# CLKB_main.net
KiCad netlist of a schematic drawn in Altium Designer
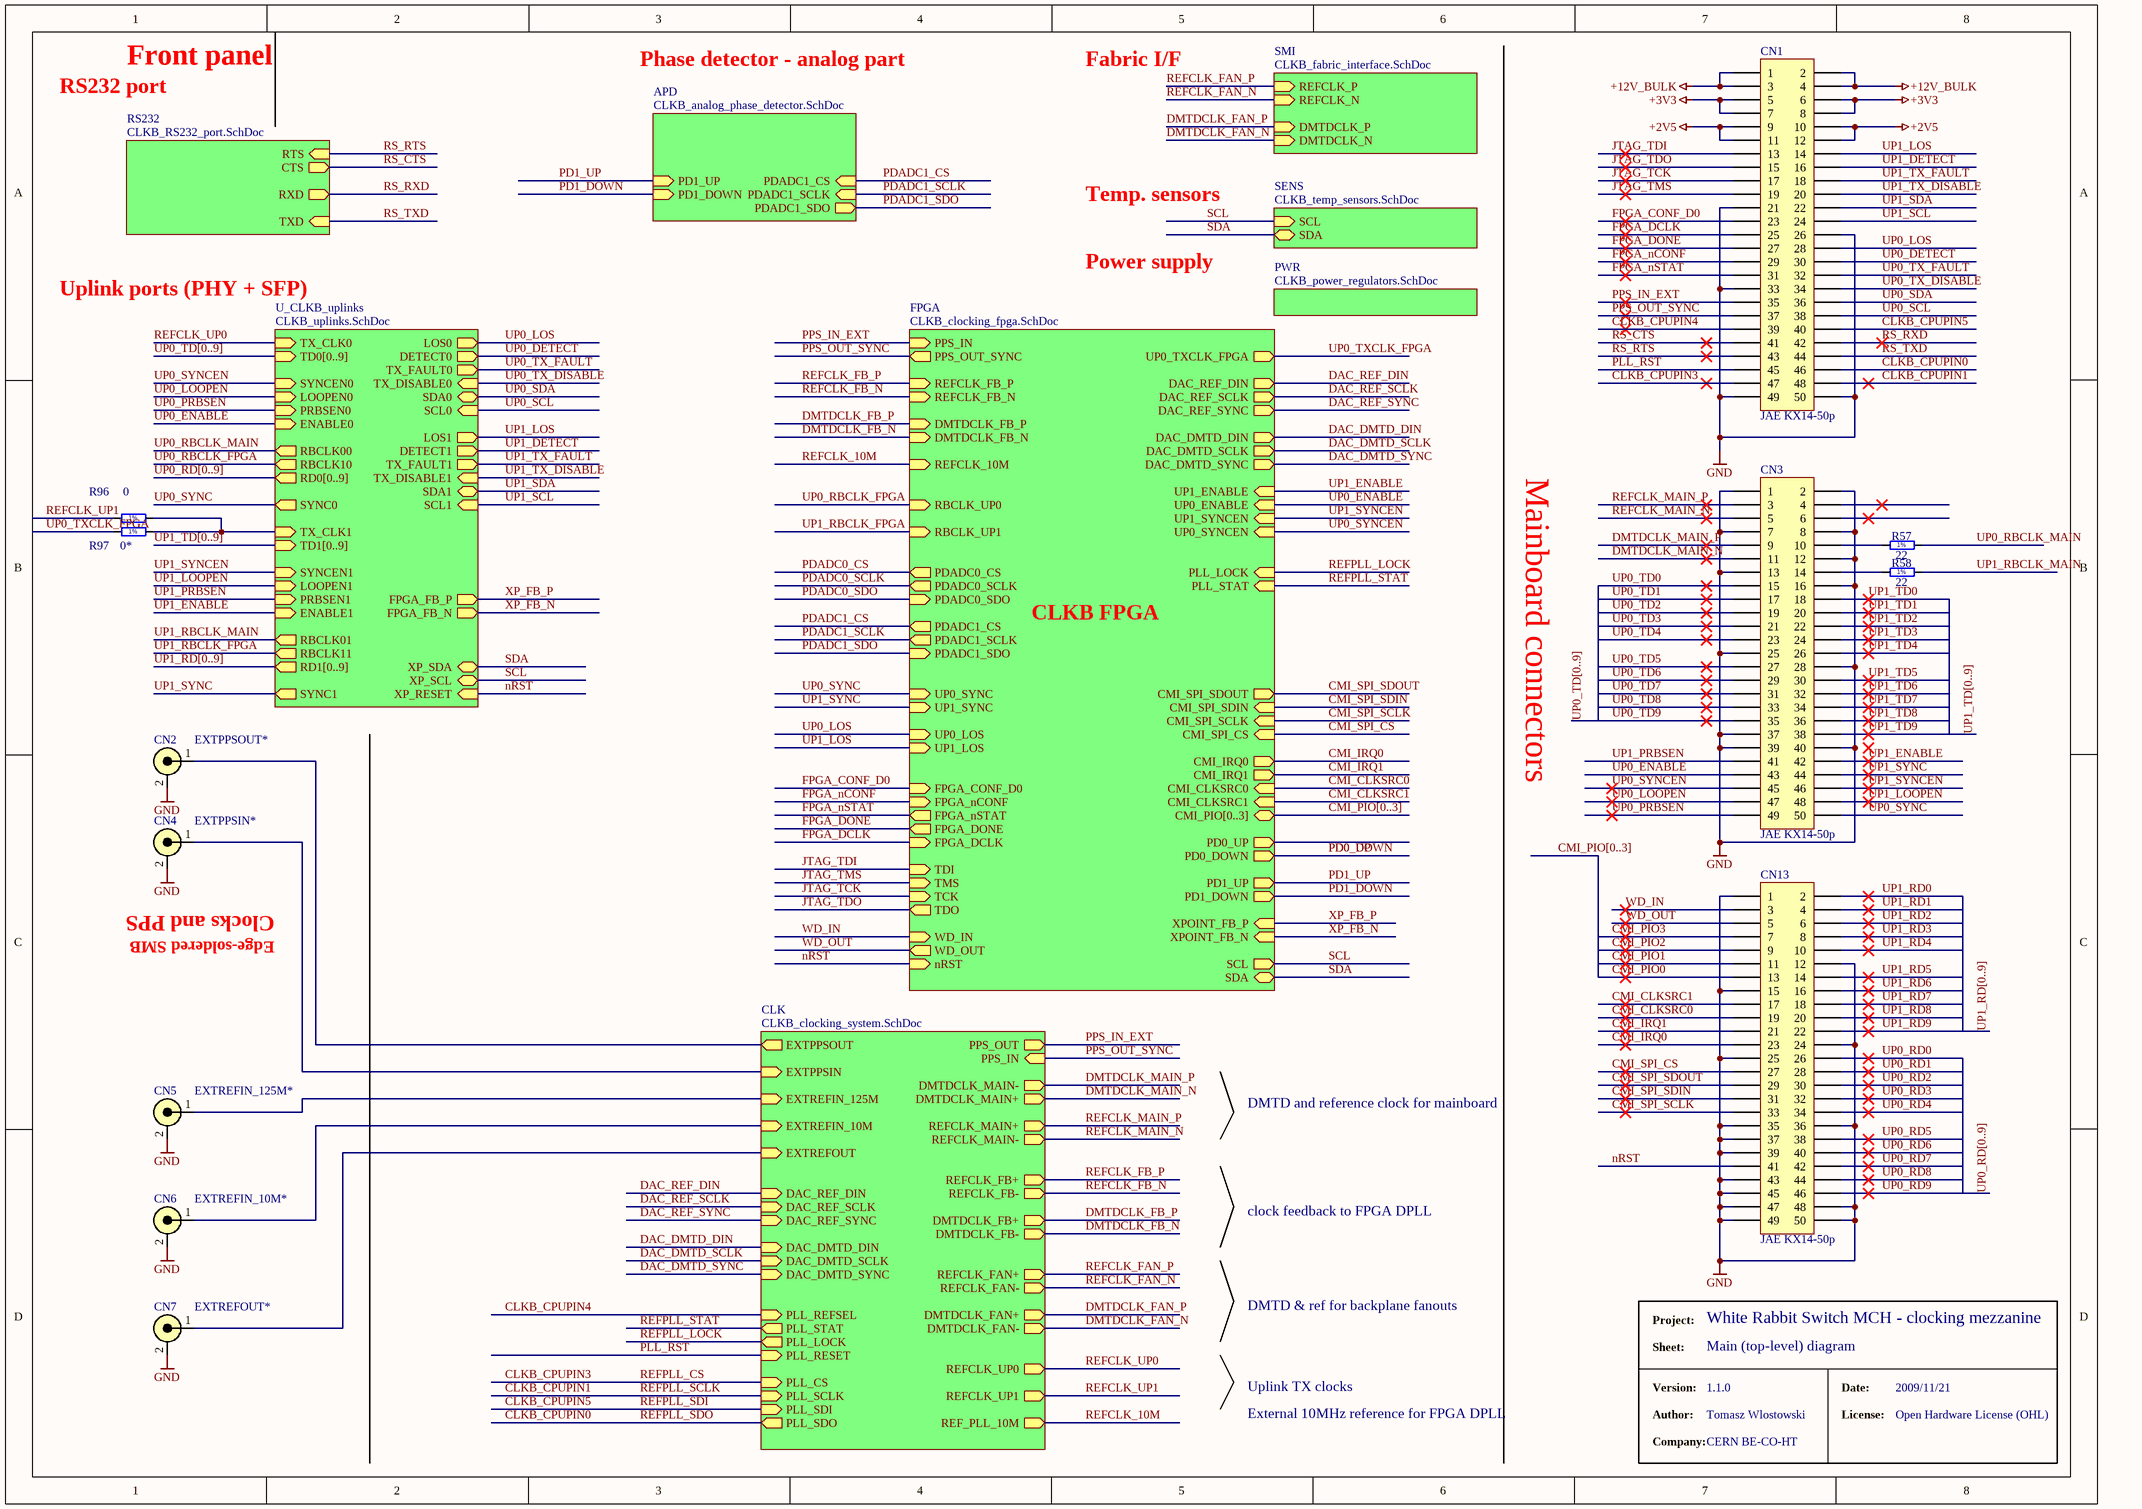
[diagram p0: CLKB_main.SchDoc]

(export (version "E")
  (design (tool "Eeschema 10.0.6"))
  (components
    (comp (ref "CN1")
      (value "JAE KX14-50p")
      (footprint "JAE_KX14_50P")
      (description "multipin B2B connector (plug)")
      (libsource (lib "wr_switch") (part "KX14_50p"))
    )
    (comp (ref "CN2")
      (value "EXTPPSOUT*")
      (footprint "MCH_SPECIAL_FP_CLOCKS")
      (description "SMB piggyboard connection")
      (libsource (lib "wr_switch") (part "SMA_SOCKET"))
    )
    (comp (ref "CN3")
      (value "JAE KX14-50p")
      (footprint "JAE_KX14_50P")
      (description "multipin B2B connector (plug)")
      (libsource (lib "wr_switch") (part "KX14_50p"))
    )
    (comp (ref "CN4")
      (value "EXTPPSIN*")
      (footprint "MCH_SPECIAL_FP_CLOCKS")
      (description "SMB piggyboard connection")
      (libsource (lib "wr_switch") (part "SMA_SOCKET"))
    )
    (comp (ref "CN5")
      (value "EXTREFIN_125M*")
      (footprint "MCH_SPECIAL_FP_CLOCKS")
      (description "SMB piggyboard connection")
      (libsource (lib "wr_switch") (part "SMA_SOCKET"))
    )
    (comp (ref "CN6")
      (value "EXTREFIN_10M*")
      (footprint "MCH_SPECIAL_FP_CLOCKS")
      (description "SMB piggyboard connection")
      (libsource (lib "wr_switch") (part "SMA_SOCKET"))
    )
    (comp (ref "CN7")
      (value "EXTREFOUT*")
      (footprint "MCH_SPECIAL_FP_CLOCKS")
      (description "SMB piggyboard connection")
      (libsource (lib "wr_switch") (part "SMA_SOCKET"))
    )
    (comp (ref "CN13")
      (value "JAE KX14-50p")
      (footprint "JAE_KX14_50P")
      (description "multipin B2B connector (plug)")
      (libsource (lib "wr_switch") (part "KX14_50p"))
    )
    (comp (ref "R57")
      (value "22")
      (footprint "RESC1608X55N")
      (description "Resistor - 1%")
      (fields
        (field (name "PART NUMBER") "R0603_22R_1%_0.1W_100PPM")
        (field (name "POWER") "0.1W")
        (field (name "AUTHOR") "CERN DEM JLC")
      )
      (libsource (lib "Resistors") (part "Resistor - 1%"))
    )
    (comp (ref "R58")
      (value "22")
      (footprint "RESC1608X55N")
      (description "Resistor - 1%")
      (fields
        (field (name "PART NUMBER") "R0603_22R_1%_0.1W_100PPM")
        (field (name "POWER") "0.1W")
        (field (name "AUTHOR") "CERN DEM JLC")
      )
      (libsource (lib "Resistors") (part "Resistor - 1%"))
    )
    (comp (ref "R96")
      (value "0")
      (footprint "RESC1005X40N")
      (description "Resistor - 1%")
      (fields
        (field (name "PART NUMBER") "R0402_0R_JUMPER")
        (field (name "MANUFACTURER") "GENERIC")
        (field (name "AUTHOR") "CERN DEM JLC")
      )
      (libsource (lib "Resistors") (part "Resistor - 1%"))
    )
    (comp (ref "R97")
      (value "0*")
      (footprint "RESC1005X40N")
      (description "Resistor - 1%")
      (fields
        (field (name "PART NUMBER") "R0402_0R_JUMPER")
        (field (name "MANUFACTURER") "GENERIC")
        (field (name "AUTHOR") "CERN DEM JLC")
      )
      (libsource (lib "Resistors") (part "Resistor - 1%"))
    )
  )
  (nets
    (net (code "1") (name "+2V5") (class "Default")
      (node (ref "CN1") (pin "10") (pinfunction "10_10") (pintype "passive"))
      (node (ref "CN1") (pin "11") (pinfunction "11_11") (pintype "passive"))
      (node (ref "CN1") (pin "12") (pinfunction "12_12") (pintype "passive"))
      (node (ref "CN1") (pin "9") (pinfunction "9_9") (pintype "passive"))
    )
    (net (code "2") (name "+3V3") (class "Default")
      (node (ref "CN1") (pin "5") (pinfunction "5_5") (pintype "passive"))
      (node (ref "CN1") (pin "6") (pinfunction "6_6") (pintype "passive"))
      (node (ref "CN1") (pin "7") (pinfunction "7_7") (pintype "passive"))
      (node (ref "CN1") (pin "8") (pinfunction "8_8") (pintype "passive"))
    )
    (net (code "3") (name "+12V_BULK") (class "Default")
      (node (ref "CN1") (pin "1") (pinfunction "1_1") (pintype "passive"))
      (node (ref "CN1") (pin "2") (pinfunction "2_2") (pintype "passive"))
      (node (ref "CN1") (pin "3") (pinfunction "3_3") (pintype "passive"))
      (node (ref "CN1") (pin "4") (pinfunction "4_4") (pintype "passive"))
    )
    (net (code "4") (name "/CLKB_CPUPIN0") (class "Default")
      (node (ref "CN1") (pin "46") (pinfunction "46_46") (pintype "passive"))
    )
    (net (code "5") (name "/CLKB_CPUPIN1") (class "Default")
      (node (ref "CN1") (pin "48") (pinfunction "48_48") (pintype "passive"))
    )
    (net (code "6") (name "/CLKB_CPUPIN3") (class "Default")
      (node (ref "CN1") (pin "47") (pinfunction "47_47") (pintype "passive"))
    )
    (net (code "7") (name "/CLKB_CPUPIN4") (class "Default")
      (node (ref "CN1") (pin "39") (pinfunction "39_39") (pintype "passive"))
    )
    (net (code "8") (name "/CLKB_CPUPIN5") (class "Default")
      (node (ref "CN1") (pin "40") (pinfunction "40_40") (pintype "passive"))
    )
    (net (code "9") (name "/CMI_CLKSRC0") (class "Default")
      (node (ref "CN13") (pin "19") (pinfunction "19_19") (pintype "passive"))
    )
    (net (code "10") (name "/CMI_CLKSRC1") (class "Default")
      (node (ref "CN13") (pin "17") (pinfunction "17_17") (pintype "passive"))
    )
    (net (code "11") (name "/CMI_IRQ0") (class "Default")
      (node (ref "CN13") (pin "23") (pinfunction "23_23") (pintype "passive"))
    )
    (net (code "12") (name "/CMI_IRQ1") (class "Default")
      (node (ref "CN13") (pin "21") (pinfunction "21_21") (pintype "passive"))
    )
    (net (code "13") (name "/CMI_PIO0") (class "Default")
      (node (ref "CN13") (pin "13") (pinfunction "13_13") (pintype "passive"))
    )
    (net (code "14") (name "/CMI_PIO1") (class "Default")
      (node (ref "CN13") (pin "11") (pinfunction "11_11") (pintype "passive"))
    )
    (net (code "15") (name "/CMI_PIO2") (class "Default")
      (node (ref "CN13") (pin "9") (pinfunction "9_9") (pintype "passive"))
    )
    (net (code "16") (name "/CMI_PIO3") (class "Default")
      (node (ref "CN13") (pin "7") (pinfunction "7_7") (pintype "passive"))
    )
    (net (code "18") (name "/CMI_SPI_CS") (class "Default")
      (node (ref "CN13") (pin "27") (pinfunction "27_27") (pintype "passive"))
    )
    (net (code "19") (name "/CMI_SPI_SCLK") (class "Default")
      (node (ref "CN13") (pin "33") (pinfunction "33_33") (pintype "passive"))
    )
    (net (code "20") (name "/CMI_SPI_SDIN") (class "Default")
      (node (ref "CN13") (pin "31") (pinfunction "31_31") (pintype "passive"))
    )
    (net (code "21") (name "/CMI_SPI_SDOUT") (class "Default")
      (node (ref "CN13") (pin "29") (pinfunction "29_29") (pintype "passive"))
    )
    (net (code "32") (name "/DMTDCLK_MAIN_N") (class "Default")
      (node (ref "CN3") (pin "11") (pinfunction "11_11") (pintype "passive"))
    )
    (net (code "33") (name "/DMTDCLK_MAIN_P") (class "Default")
      (node (ref "CN3") (pin "9") (pinfunction "9_9") (pintype "passive"))
    )
    (net (code "34") (name "/EXTPPSIN") (class "Default")
      (node (ref "CN4") (pin "1") (pinfunction "HOT_1") (pintype "passive"))
    )
    (net (code "35") (name "/EXTPPSOUT") (class "Default")
      (node (ref "CN2") (pin "1") (pinfunction "HOT_1") (pintype "passive"))
    )
    (net (code "36") (name "/EXTREFIN_10M") (class "Default")
      (node (ref "CN6") (pin "1") (pinfunction "HOT_1") (pintype "passive"))
    )
    (net (code "37") (name "/EXTREFIN_125M") (class "Default")
      (node (ref "CN5") (pin "1") (pinfunction "HOT_1") (pintype "passive"))
    )
    (net (code "38") (name "/EXTREFOUT") (class "Default")
      (node (ref "CN7") (pin "1") (pinfunction "HOT_1") (pintype "passive"))
    )
    (net (code "39") (name "/FPGA_CONF_D0") (class "Default")
      (node (ref "CN1") (pin "23") (pinfunction "23_23") (pintype "passive"))
    )
    (net (code "40") (name "/FPGA_DCLK") (class "Default")
      (node (ref "CN1") (pin "25") (pinfunction "25_25") (pintype "passive"))
    )
    (net (code "41") (name "/FPGA_DONE") (class "Default")
      (node (ref "CN1") (pin "27") (pinfunction "27_27") (pintype "passive"))
    )
    (net (code "42") (name "/FPGA_nCONF") (class "Default")
      (node (ref "CN1") (pin "29") (pinfunction "29_29") (pintype "passive"))
    )
    (net (code "43") (name "/FPGA_nSTAT") (class "Default")
      (node (ref "CN1") (pin "31") (pinfunction "31_31") (pintype "passive"))
    )
    (net (code "44") (name "/JTAG_TCK") (class "Default")
      (node (ref "CN1") (pin "17") (pinfunction "17_17") (pintype "passive"))
    )
    (net (code "45") (name "/JTAG_TDI") (class "Default")
      (node (ref "CN1") (pin "13") (pinfunction "13_13") (pintype "passive"))
    )
    (net (code "46") (name "/JTAG_TDO") (class "Default")
      (node (ref "CN1") (pin "15") (pinfunction "15_15") (pintype "passive"))
    )
    (net (code "47") (name "/JTAG_TMS") (class "Default")
      (node (ref "CN1") (pin "19") (pinfunction "19_19") (pintype "passive"))
    )
    (net (code "57") (name "/PLL_RST") (class "Default")
      (node (ref "CN1") (pin "45") (pinfunction "45_45") (pintype "passive"))
    )
    (net (code "58") (name "/PPS_IN_EXT") (class "Default")
      (node (ref "CN1") (pin "35") (pinfunction "35_35") (pintype "passive"))
    )
    (net (code "59") (name "/PPS_OUT_SYNC") (class "Default")
      (node (ref "CN1") (pin "37") (pinfunction "37_37") (pintype "passive"))
    )
    (net (code "65") (name "/REFCLK_MAIN_N") (class "Default")
      (node (ref "CN3") (pin "5") (pinfunction "5_5") (pintype "passive"))
    )
    (net (code "66") (name "/REFCLK_MAIN_P") (class "Default")
      (node (ref "CN3") (pin "3") (pinfunction "3_3") (pintype "passive"))
    )
    (net (code "68") (name "/REFCLK_UP1") (class "Default")
      (node (ref "R96") (pin "1") (pinfunction "1_1") (pintype "passive"))
    )
    (net (code "71") (name "/RS_CTS") (class "Default")
      (node (ref "CN1") (pin "41") (pinfunction "41_41") (pintype "passive"))
    )
    (net (code "72") (name "/RS_RTS") (class "Default")
      (node (ref "CN1") (pin "43") (pinfunction "43_43") (pintype "passive"))
    )
    (net (code "74") (name "/RS_RXD") (class "Default")
      (node (ref "CN1") (pin "42") (pinfunction "42_42") (pintype "passive"))
    )
    (net (code "77") (name "/RS_TXD") (class "Default")
      (node (ref "CN1") (pin "44") (pinfunction "44_44") (pintype "passive"))
    )
    (net (code "78") (name "/TX_CLK1") (class "Default")
      (node (ref "R96") (pin "2") (pinfunction "2_2") (pintype "passive"))
      (node (ref "R97") (pin "2") (pinfunction "2_2") (pintype "passive"))
    )
    (net (code "79") (name "/UP0_DETECT") (class "Default")
      (node (ref "CN1") (pin "30") (pinfunction "30_30") (pintype "passive"))
    )
    (net (code "81") (name "/UP0_ENABLE") (class "Default")
      (node (ref "CN3") (pin "43") (pinfunction "43_43") (pintype "passive"))
    )
    (net (code "84") (name "/UP0_LOOPEN") (class "Default")
      (node (ref "CN3") (pin "47") (pinfunction "47_47") (pintype "passive"))
    )
    (net (code "85") (name "/UP0_LOS") (class "Default")
      (node (ref "CN1") (pin "28") (pinfunction "28_28") (pintype "passive"))
    )
    (net (code "86") (name "/UP0_PRBSEN") (class "Default")
      (node (ref "CN3") (pin "49") (pinfunction "49_49") (pintype "passive"))
    )
    (net (code "87") (name "/UP0_RBCLK_MAIN") (class "Default")
      (node (ref "R57") (pin "2") (pinfunction "2_2") (pintype "passive"))
    )
    (net (code "88") (name "/UP0_RD0") (class "Default")
      (node (ref "CN13") (pin "26") (pinfunction "26_26") (pintype "passive"))
    )
    (net (code "89") (name "/UP0_RD1") (class "Default")
      (node (ref "CN13") (pin "28") (pinfunction "28_28") (pintype "passive"))
    )
    (net (code "90") (name "/UP0_RD2") (class "Default")
      (node (ref "CN13") (pin "30") (pinfunction "30_30") (pintype "passive"))
    )
    (net (code "91") (name "/UP0_RD3") (class "Default")
      (node (ref "CN13") (pin "32") (pinfunction "32_32") (pintype "passive"))
    )
    (net (code "92") (name "/UP0_RD4") (class "Default")
      (node (ref "CN13") (pin "34") (pinfunction "34_34") (pintype "passive"))
    )
    (net (code "93") (name "/UP0_RD5") (class "Default")
      (node (ref "CN13") (pin "38") (pinfunction "38_38") (pintype "passive"))
    )
    (net (code "94") (name "/UP0_RD6") (class "Default")
      (node (ref "CN13") (pin "40") (pinfunction "40_40") (pintype "passive"))
    )
    (net (code "96") (name "/UP0_RD7") (class "Default")
      (node (ref "CN13") (pin "42") (pinfunction "42_42") (pintype "passive"))
    )
    (net (code "97") (name "/UP0_RD8") (class "Default")
      (node (ref "CN13") (pin "44") (pinfunction "44_44") (pintype "passive"))
    )
    (net (code "98") (name "/UP0_RD9") (class "Default")
      (node (ref "CN13") (pin "46") (pinfunction "46_46") (pintype "passive"))
    )
    (net (code "100") (name "/UP0_SCL") (class "Default")
      (node (ref "CN1") (pin "38") (pinfunction "38_38") (pintype "passive"))
    )
    (net (code "101") (name "/UP0_SDA") (class "Default")
      (node (ref "CN1") (pin "36") (pinfunction "36_36") (pintype "passive"))
    )
    (net (code "102") (name "/UP0_SYNC") (class "Default")
      (node (ref "CN3") (pin "50") (pinfunction "50_50") (pintype "passive"))
    )
    (net (code "103") (name "/UP0_SYNCEN") (class "Default")
      (node (ref "CN3") (pin "45") (pinfunction "45_45") (pintype "passive"))
    )
    (net (code "104") (name "/UP0_TD0") (class "Default")
      (node (ref "CN3") (pin "15") (pinfunction "15_15") (pintype "passive"))
    )
    (net (code "105") (name "/UP0_TD1") (class "Default")
      (node (ref "CN3") (pin "17") (pinfunction "17_17") (pintype "passive"))
    )
    (net (code "106") (name "/UP0_TD2") (class "Default")
      (node (ref "CN3") (pin "19") (pinfunction "19_19") (pintype "passive"))
    )
    (net (code "107") (name "/UP0_TD3") (class "Default")
      (node (ref "CN3") (pin "21") (pinfunction "21_21") (pintype "passive"))
    )
    (net (code "108") (name "/UP0_TD4") (class "Default")
      (node (ref "CN3") (pin "23") (pinfunction "23_23") (pintype "passive"))
    )
    (net (code "109") (name "/UP0_TD5") (class "Default")
      (node (ref "CN3") (pin "27") (pinfunction "27_27") (pintype "passive"))
    )
    (net (code "111") (name "/UP0_TD6") (class "Default")
      (node (ref "CN3") (pin "29") (pinfunction "29_29") (pintype "passive"))
    )
    (net (code "112") (name "/UP0_TD7") (class "Default")
      (node (ref "CN3") (pin "31") (pinfunction "31_31") (pintype "passive"))
    )
    (net (code "113") (name "/UP0_TD8") (class "Default")
      (node (ref "CN3") (pin "33") (pinfunction "33_33") (pintype "passive"))
    )
    (net (code "114") (name "/UP0_TD9") (class "Default")
      (node (ref "CN3") (pin "35") (pinfunction "35_35") (pintype "passive"))
    )
    (net (code "117") (name "/UP0_TXCLK_FPGA") (class "Default")
      (node (ref "R97") (pin "1") (pinfunction "1_1") (pintype "passive"))
    )
    (net (code "118") (name "/UP0_TX_DISABLE") (class "Default")
      (node (ref "CN1") (pin "34") (pinfunction "34_34") (pintype "passive"))
    )
    (net (code "120") (name "/UP0_TX_FAULT") (class "Default")
      (node (ref "CN1") (pin "32") (pinfunction "32_32") (pintype "passive"))
    )
    (net (code "121") (name "/UP1_DETECT") (class "Default")
      (node (ref "CN1") (pin "16") (pinfunction "16_16") (pintype "passive"))
    )
    (net (code "122") (name "/UP1_ENABLE") (class "Default")
      (node (ref "CN3") (pin "42") (pinfunction "42_42") (pintype "passive"))
    )
    (net (code "123") (name "/UP1_LOOPEN") (class "Default")
      (node (ref "CN3") (pin "48") (pinfunction "48_48") (pintype "passive"))
    )
    (net (code "124") (name "/UP1_LOS") (class "Default")
      (node (ref "CN1") (pin "14") (pinfunction "14_14") (pintype "passive"))
    )
    (net (code "125") (name "/UP1_PRBSEN") (class "Default")
      (node (ref "CN3") (pin "41") (pinfunction "41_41") (pintype "passive"))
    )
    (net (code "126") (name "/UP1_RBCLK_MAIN") (class "Default")
      (node (ref "R58") (pin "2") (pinfunction "2_2") (pintype "passive"))
    )
    (net (code "127") (name "/UP1_RD0") (class "Default")
      (node (ref "CN13") (pin "2") (pinfunction "2_2") (pintype "passive"))
    )
    (net (code "128") (name "/UP1_RD1") (class "Default")
      (node (ref "CN13") (pin "4") (pinfunction "4_4") (pintype "passive"))
    )
    (net (code "129") (name "/UP1_RD2") (class "Default")
      (node (ref "CN13") (pin "6") (pinfunction "6_6") (pintype "passive"))
    )
    (net (code "130") (name "/UP1_RD3") (class "Default")
      (node (ref "CN13") (pin "8") (pinfunction "8_8") (pintype "passive"))
    )
    (net (code "132") (name "/UP1_RD4") (class "Default")
      (node (ref "CN13") (pin "10") (pinfunction "10_10") (pintype "passive"))
    )
    (net (code "133") (name "/UP1_RD5") (class "Default")
      (node (ref "CN13") (pin "14") (pinfunction "14_14") (pintype "passive"))
    )
    (net (code "147") (name "/UP1_RD6") (class "Default")
      (node (ref "CN13") (pin "16") (pinfunction "16_16") (pintype "passive"))
    )
    (net (code "148") (name "/UP1_RD7") (class "Default")
      (node (ref "CN13") (pin "18") (pinfunction "18_18") (pintype "passive"))
    )
    (net (code "153") (name "/UP1_RD8") (class "Default")
      (node (ref "CN13") (pin "20") (pinfunction "20_20") (pintype "passive"))
    )
    (net (code "154") (name "/UP1_RD9") (class "Default")
      (node (ref "CN13") (pin "22") (pinfunction "22_22") (pintype "passive"))
    )
    (net (code "155") (name "/UP1_SCL") (class "Default")
      (node (ref "CN1") (pin "24") (pinfunction "24_24") (pintype "passive"))
    )
    (net (code "156") (name "/UP1_SDA") (class "Default")
      (node (ref "CN1") (pin "22") (pinfunction "22_22") (pintype "passive"))
    )
    (net (code "157") (name "/UP1_SYNC") (class "Default")
      (node (ref "CN3") (pin "44") (pinfunction "44_44") (pintype "passive"))
    )
    (net (code "158") (name "/UP1_SYNCEN") (class "Default")
      (node (ref "CN3") (pin "46") (pinfunction "46_46") (pintype "passive"))
    )
    (net (code "159") (name "/UP1_TD0") (class "Default")
      (node (ref "CN3") (pin "18") (pinfunction "18_18") (pintype "passive"))
    )
    (net (code "160") (name "/UP1_TD1") (class "Default")
      (node (ref "CN3") (pin "20") (pinfunction "20_20") (pintype "passive"))
    )
    (net (code "161") (name "/UP1_TD2") (class "Default")
      (node (ref "CN3") (pin "22") (pinfunction "22_22") (pintype "passive"))
    )
    (net (code "162") (name "/UP1_TD3") (class "Default")
      (node (ref "CN3") (pin "24") (pinfunction "24_24") (pintype "passive"))
    )
    (net (code "163") (name "/UP1_TD4") (class "Default")
      (node (ref "CN3") (pin "26") (pinfunction "26_26") (pintype "passive"))
    )
    (net (code "164") (name "/UP1_TD5") (class "Default")
      (node (ref "CN3") (pin "30") (pinfunction "30_30") (pintype "passive"))
    )
    (net (code "165") (name "/UP1_TD6") (class "Default")
      (node (ref "CN3") (pin "32") (pinfunction "32_32") (pintype "passive"))
    )
    (net (code "166") (name "/UP1_TD7") (class "Default")
      (node (ref "CN3") (pin "34") (pinfunction "34_34") (pintype "passive"))
    )
    (net (code "167") (name "/UP1_TD8") (class "Default")
      (node (ref "CN3") (pin "36") (pinfunction "36_36") (pintype "passive"))
    )
    (net (code "168") (name "/UP1_TD9") (class "Default")
      (node (ref "CN3") (pin "38") (pinfunction "38_38") (pintype "passive"))
    )
    (net (code "169") (name "/UP1_TX_DISABLE") (class "Default")
      (node (ref "CN1") (pin "20") (pinfunction "20_20") (pintype "passive"))
    )
    (net (code "170") (name "/UP1_TX_FAULT") (class "Default")
      (node (ref "CN1") (pin "18") (pinfunction "18_18") (pintype "passive"))
    )
    (net (code "171") (name "/WD_IN") (class "Default")
      (node (ref "CN13") (pin "3") (pinfunction "3_3") (pintype "passive"))
    )
    (net (code "172") (name "/WD_OUT") (class "Default")
      (node (ref "CN13") (pin "5") (pinfunction "5_5") (pintype "passive"))
    )
    (net (code "173") (name "/nRST") (class "Default")
      (node (ref "CN13") (pin "41") (pinfunction "41_41") (pintype "passive"))
    )
    (net (code "174") (name "GND") (class "Default")
      (node (ref "CN1") (pin "21") (pinfunction "21_21") (pintype "passive"))
      (node (ref "CN1") (pin "26") (pinfunction "26_26") (pintype "passive"))
      (node (ref "CN1") (pin "33") (pinfunction "33_33") (pintype "passive"))
      (node (ref "CN1") (pin "49") (pinfunction "49_49") (pintype "passive"))
      (node (ref "CN1") (pin "50") (pinfunction "50_50") (pintype "passive"))
      (node (ref "CN13") (pin "1") (pinfunction "1_1") (pintype "passive"))
      (node (ref "CN13") (pin "12") (pinfunction "12_12") (pintype "passive"))
      (node (ref "CN13") (pin "15") (pinfunction "15_15") (pintype "passive"))
      (node (ref "CN13") (pin "24") (pinfunction "24_24") (pintype "passive"))
      (node (ref "CN13") (pin "25") (pinfunction "25_25") (pintype "passive"))
      (node (ref "CN13") (pin "35") (pinfunction "35_35") (pintype "passive"))
      (node (ref "CN13") (pin "36") (pinfunction "36_36") (pintype "passive"))
      (node (ref "CN13") (pin "37") (pinfunction "37_37") (pintype "passive"))
      (node (ref "CN13") (pin "39") (pinfunction "39_39") (pintype "passive"))
      (node (ref "CN13") (pin "43") (pinfunction "43_43") (pintype "passive"))
      (node (ref "CN13") (pin "45") (pinfunction "45_45") (pintype "passive"))
      (node (ref "CN13") (pin "47") (pinfunction "47_47") (pintype "passive"))
      (node (ref "CN13") (pin "48") (pinfunction "48_48") (pintype "passive"))
      (node (ref "CN13") (pin "49") (pinfunction "49_49") (pintype "passive"))
      (node (ref "CN13") (pin "50") (pinfunction "50_50") (pintype "passive"))
      (node (ref "CN2") (pin "2") (pinfunction "GND_2") (pintype "passive"))
      (node (ref "CN3") (pin "1") (pinfunction "1_1") (pintype "passive"))
      (node (ref "CN3") (pin "12") (pinfunction "12_12") (pintype "passive"))
      (node (ref "CN3") (pin "13") (pinfunction "13_13") (pintype "passive"))
      (node (ref "CN3") (pin "16") (pinfunction "16_16") (pintype "passive"))
      (node (ref "CN3") (pin "2") (pinfunction "2_2") (pintype "passive"))
      (node (ref "CN3") (pin "25") (pinfunction "25_25") (pintype "passive"))
      (node (ref "CN3") (pin "28") (pinfunction "28_28") (pintype "passive"))
      (node (ref "CN3") (pin "37") (pinfunction "37_37") (pintype "passive"))
      (node (ref "CN3") (pin "39") (pinfunction "39_39") (pintype "passive"))
      (node (ref "CN3") (pin "40") (pinfunction "40_40") (pintype "passive"))
      (node (ref "CN3") (pin "7") (pinfunction "7_7") (pintype "passive"))
      (node (ref "CN3") (pin "8") (pinfunction "8_8") (pintype "passive"))
      (node (ref "CN4") (pin "2") (pinfunction "GND_2") (pintype "passive"))
      (node (ref "CN5") (pin "2") (pinfunction "GND_2") (pintype "passive"))
      (node (ref "CN6") (pin "2") (pinfunction "GND_2") (pintype "passive"))
      (node (ref "CN7") (pin "2") (pinfunction "GND_2") (pintype "passive"))
    )
    (net (code "175") (name "Net-(CN3-Pad10)") (class "Default")
      (node (ref "CN3") (pin "10") (pinfunction "10_10") (pintype "passive"))
      (node (ref "R57") (pin "1") (pinfunction "1_1") (pintype "passive"))
    )
    (net (code "176") (name "Net-(CN3-Pad14)") (class "Default")
      (node (ref "CN3") (pin "14") (pinfunction "14_14") (pintype "passive"))
      (node (ref "R58") (pin "1") (pinfunction "1_1") (pintype "passive"))
    )
    (net (code "177") (name "unconnected-(CN3-Pad4)") (class "Default")
      (node (ref "CN3") (pin "4") (pinfunction "4_4") (pintype "passive"))
    )
    (net (code "178") (name "unconnected-(CN3-Pad6)") (class "Default")
      (node (ref "CN3") (pin "6") (pinfunction "6_6") (pintype "passive"))
    )
  )
)
